# bbc_micro.net
KiCad netlist of a schematic drawn in EAGLE
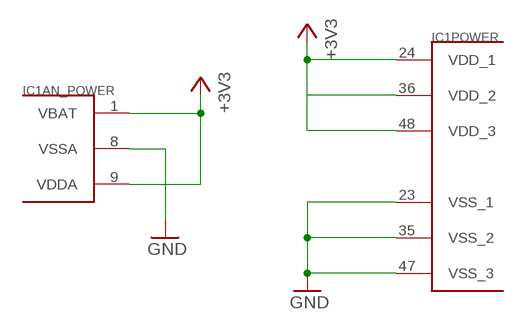
[diagram p0: schematic, sheet 1, part 1 of 2]
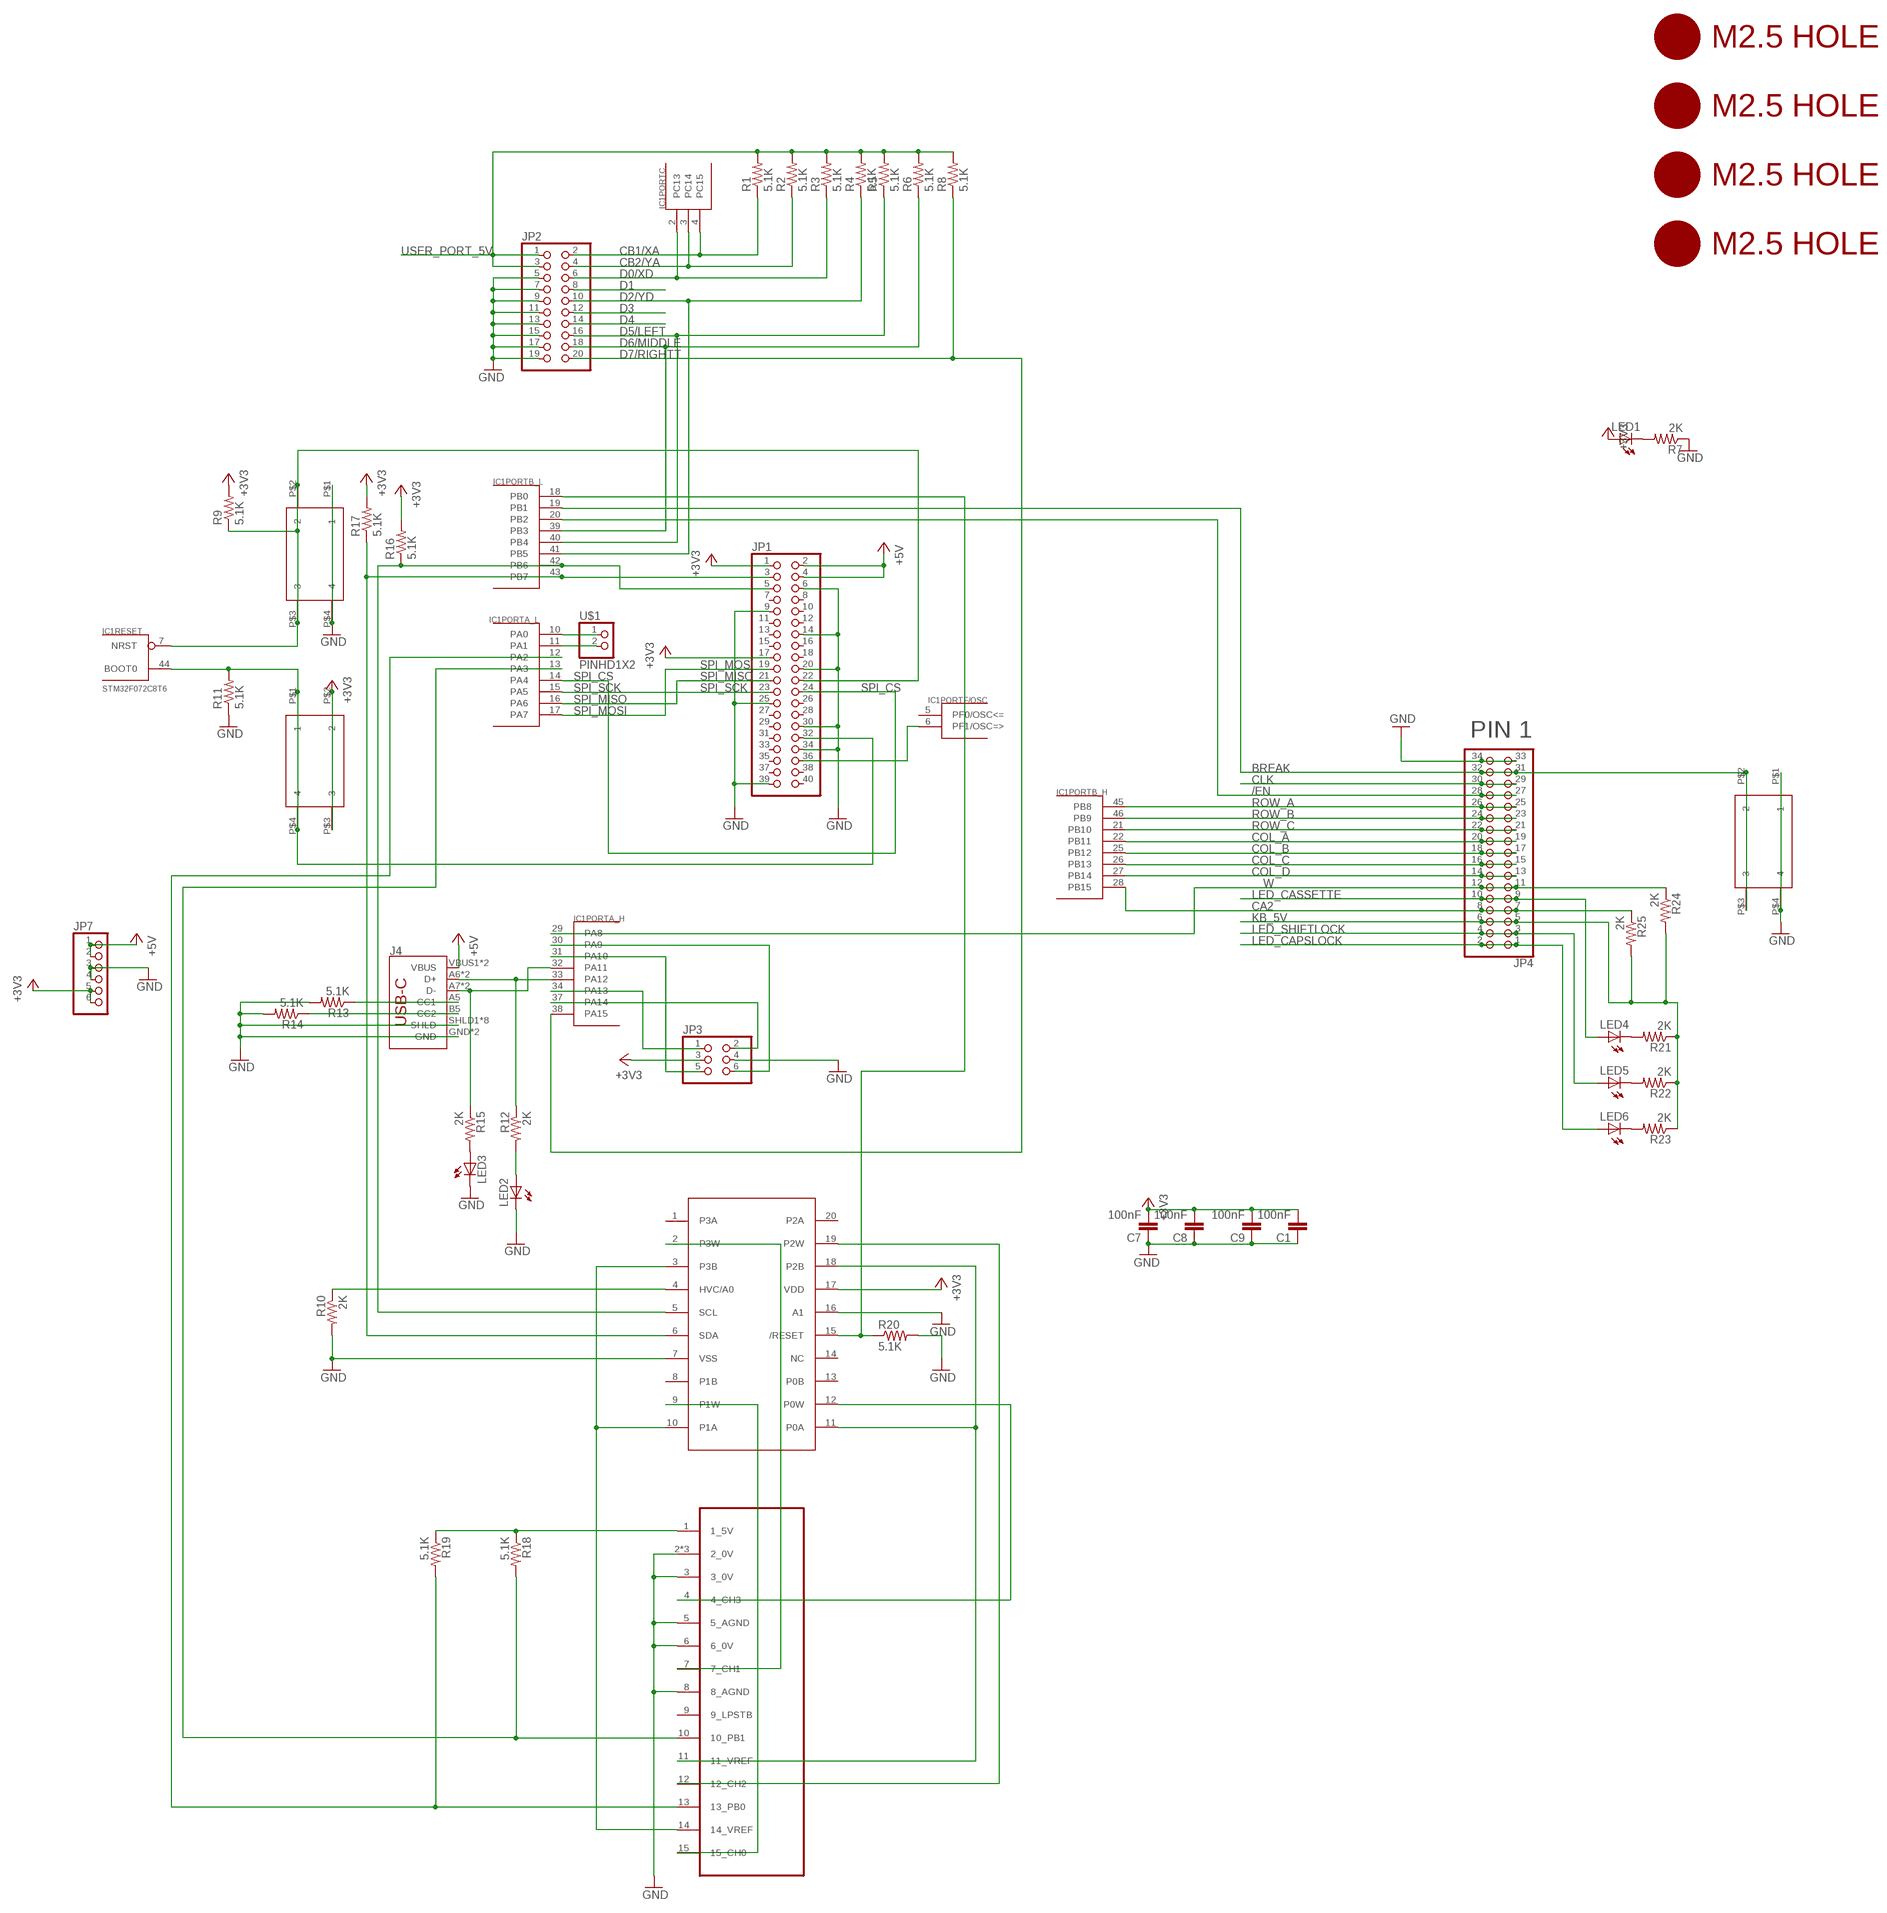
[diagram p1: schematic, sheet 1, part 2 of 2]

(export (version "E")
  (design (tool "Eeschema 10.0.6"))
  (components
    (comp (ref "C1")
      (value "100nF")
      (footprint "eagle-import:0805@1")
      (libsource (lib "eagle-import") (part "CAP0805"))
    )
    (comp (ref "C7")
      (value "100nF")
      (footprint "eagle-import:0805@1")
      (libsource (lib "eagle-import") (part "CAP0805"))
    )
    (comp (ref "C8")
      (value "100nF")
      (footprint "eagle-import:0805@1")
      (libsource (lib "eagle-import") (part "CAP0805"))
    )
    (comp (ref "C9")
      (value "100nF")
      (footprint "eagle-import:0805@1")
      (libsource (lib "eagle-import") (part "CAP0805"))
    )
    (comp (ref "IC1")
      (value "STM32F072C8T6")
      (footprint "eagle-import:TQFP48")
      (libsource (lib "eagle-import") (part "STM32F072C8T6"))
    )
    (comp (ref "J4")
      (value "USB_C16PIN")
      (footprint "eagle-import:USB-C-16P")
      (libsource (lib "eagle-import") (part "USB_C16PIN"))
    )
    (comp (ref "JP1")
      (value "PINHD-2X20-BIG")
      (footprint "eagle-import:2X20-BIG")
      (libsource (lib "eagle-import") (part "PINHD-2X20-BIG"))
    )
    (comp (ref "JP2")
      (value "PINHD-2X10/90")
      (footprint "eagle-import:2X10_90")
      (libsource (lib "eagle-import") (part "PINHD-2X10/90"))
    )
    (comp (ref "JP3")
      (value "PINHD-2X3")
      (footprint "eagle-import:2X03")
      (libsource (lib "eagle-import") (part "PINHD-2X3"))
    )
    (comp (ref "JP4")
      (value "PINHD-2X17/90")
      (footprint "eagle-import:2X17_90")
      (libsource (lib "eagle-import") (part "PINHD-2X17/90"))
    )
    (comp (ref "JP7")
      (value "PINHD-1X6CB")
      (footprint "eagle-import:1X06-CLEANBIG")
      (libsource (lib "eagle-import") (part "PINHD-1X6CB"))
    )
    (comp (ref "LED1")
      (value "LEDCHIP-LED0805")
      (footprint "eagle-import:CHIP-LED0805")
      (libsource (lib "eagle-import") (part "LEDCHIP-LED0805"))
    )
    (comp (ref "LED2")
      (value "LEDCHIP-LED0805")
      (footprint "eagle-import:CHIP-LED0805")
      (libsource (lib "eagle-import") (part "LEDCHIP-LED0805"))
    )
    (comp (ref "LED3")
      (value "LEDCHIP-LED0805")
      (footprint "eagle-import:CHIP-LED0805")
      (libsource (lib "eagle-import") (part "LEDCHIP-LED0805"))
    )
    (comp (ref "LED4")
      (value "LEDCHIP-LED0805")
      (footprint "eagle-import:CHIP-LED0805")
      (libsource (lib "eagle-import") (part "LEDCHIP-LED0805"))
    )
    (comp (ref "LED5")
      (value "LEDCHIP-LED0805")
      (footprint "eagle-import:CHIP-LED0805")
      (libsource (lib "eagle-import") (part "LEDCHIP-LED0805"))
    )
    (comp (ref "LED6")
      (value "LEDCHIP-LED0805")
      (footprint "eagle-import:CHIP-LED0805")
      (libsource (lib "eagle-import") (part "LEDCHIP-LED0805"))
    )
    (comp (ref "R1")
      (value "5.1K")
      (footprint "eagle-import:0805")
      (libsource (lib "eagle-import") (part "RESISTOR0805-RES"))
    )
    (comp (ref "R2")
      (value "5.1K")
      (footprint "eagle-import:0805")
      (libsource (lib "eagle-import") (part "RESISTOR0805-RES"))
    )
    (comp (ref "R3")
      (value "5.1K")
      (footprint "eagle-import:0805")
      (libsource (lib "eagle-import") (part "RESISTOR0805-RES"))
    )
    (comp (ref "R4")
      (value "5.1K")
      (footprint "eagle-import:0805")
      (libsource (lib "eagle-import") (part "RESISTOR0805-RES"))
    )
    (comp (ref "R5")
      (value "5.1K")
      (footprint "eagle-import:0805")
      (libsource (lib "eagle-import") (part "RESISTOR0805-RES"))
    )
    (comp (ref "R6")
      (value "5.1K")
      (footprint "eagle-import:0805")
      (libsource (lib "eagle-import") (part "RESISTOR0805-RES"))
    )
    (comp (ref "R7")
      (value "2K")
      (footprint "eagle-import:0805")
      (libsource (lib "eagle-import") (part "RESISTOR0805-RES"))
    )
    (comp (ref "R8")
      (value "5.1K")
      (footprint "eagle-import:0805")
      (libsource (lib "eagle-import") (part "RESISTOR0805-RES"))
    )
    (comp (ref "R9")
      (value "5.1K")
      (footprint "eagle-import:0805")
      (libsource (lib "eagle-import") (part "RESISTOR0805-RES"))
    )
    (comp (ref "R10")
      (value "2K")
      (footprint "eagle-import:0805")
      (libsource (lib "eagle-import") (part "RESISTOR0805-RES"))
    )
    (comp (ref "R11")
      (value "5.1K")
      (footprint "eagle-import:0805")
      (libsource (lib "eagle-import") (part "RESISTOR0805-RES"))
    )
    (comp (ref "R12")
      (value "2K")
      (footprint "eagle-import:0805")
      (libsource (lib "eagle-import") (part "RESISTOR0805-RES"))
    )
    (comp (ref "R13")
      (value "5.1K")
      (footprint "eagle-import:0805")
      (libsource (lib "eagle-import") (part "RESISTOR0805-RES"))
    )
    (comp (ref "R14")
      (value "5.1K")
      (footprint "eagle-import:0805")
      (libsource (lib "eagle-import") (part "RESISTOR0805-RES"))
    )
    (comp (ref "R15")
      (value "2K")
      (footprint "eagle-import:0805")
      (libsource (lib "eagle-import") (part "RESISTOR0805-RES"))
    )
    (comp (ref "R16")
      (value "5.1K")
      (footprint "eagle-import:0805")
      (libsource (lib "eagle-import") (part "RESISTOR0805-RES"))
    )
    (comp (ref "R17")
      (value "5.1K")
      (footprint "eagle-import:0805")
      (libsource (lib "eagle-import") (part "RESISTOR0805-RES"))
    )
    (comp (ref "R18")
      (value "5.1K")
      (footprint "eagle-import:0805")
      (libsource (lib "eagle-import") (part "RESISTOR0805-RES"))
    )
    (comp (ref "R19")
      (value "5.1K")
      (footprint "eagle-import:0805")
      (libsource (lib "eagle-import") (part "RESISTOR0805-RES"))
    )
    (comp (ref "R20")
      (value "5.1K")
      (footprint "eagle-import:0805")
      (libsource (lib "eagle-import") (part "RESISTOR0805-RES"))
    )
    (comp (ref "R21")
      (value "2K")
      (footprint "eagle-import:0805")
      (libsource (lib "eagle-import") (part "RESISTOR0805-RES"))
    )
    (comp (ref "R22")
      (value "2K")
      (footprint "eagle-import:0805")
      (libsource (lib "eagle-import") (part "RESISTOR0805-RES"))
    )
    (comp (ref "R23")
      (value "2K")
      (footprint "eagle-import:0805")
      (libsource (lib "eagle-import") (part "RESISTOR0805-RES"))
    )
    (comp (ref "R24")
      (value "2K")
      (footprint "eagle-import:0805")
      (libsource (lib "eagle-import") (part "RESISTOR0805-RES"))
    )
    (comp (ref "R25")
      (value "2K")
      (footprint "eagle-import:0805")
      (libsource (lib "eagle-import") (part "RESISTOR0805-RES"))
    )
    (comp (ref "SW1")
      (value "324_SW")
      (footprint "eagle-import:342_SWICH_FOOT")
      (libsource (lib "eagle-import") (part "324_SW"))
    )
    (comp (ref "SW2")
      (value "324_SW")
      (footprint "eagle-import:342_SWICH_FOOT")
      (libsource (lib "eagle-import") (part "324_SW"))
    )
    (comp (ref "SW3")
      (value "324_SW")
      (footprint "eagle-import:342_SWICH_FOOT")
      (libsource (lib "eagle-import") (part "324_SW"))
    )
    (comp (ref "U$1")
      (value "PINHD1X2")
      (footprint "eagle-import:1X02")
      (libsource (lib "eagle-import") (part "PINHD1X2"))
    )
    (comp (ref "U$2")
      (value "M2.5HOLE")
      (footprint "eagle-import:M2.5HOLE")
      (libsource (lib "eagle-import") (part "M2.5HOLE"))
    )
    (comp (ref "U$3")
      (value "M2.5HOLE")
      (footprint "eagle-import:M2.5HOLE")
      (libsource (lib "eagle-import") (part "M2.5HOLE"))
    )
    (comp (ref "U$5")
      (value "MCP4451")
      (footprint "eagle-import:TSSOP20")
      (libsource (lib "eagle-import") (part "MCP4451"))
    )
    (comp (ref "U$6")
      (value "M2.5HOLE")
      (footprint "eagle-import:M2.5HOLE")
      (libsource (lib "eagle-import") (part "M2.5HOLE"))
    )
    (comp (ref "U$7")
      (value "M2.5HOLE")
      (footprint "eagle-import:M2.5HOLE")
      (libsource (lib "eagle-import") (part "M2.5HOLE"))
    )
    (comp (ref "U$9")
      (value "BBC_15P")
      (footprint "eagle-import:DA15")
      (libsource (lib "eagle-import") (part "BBC_15P"))
    )
  )
  (nets
    (net (code "1") (name "+3V3") (class "Default")
      (node (ref "C1") (pin "2") (pinfunction "2_2") (pintype "passive"))
      (node (ref "C7") (pin "2") (pinfunction "2_2") (pintype "passive"))
      (node (ref "C8") (pin "2") (pinfunction "2_2") (pintype "passive"))
      (node (ref "C9") (pin "2") (pinfunction "2_2") (pintype "passive"))
      (node (ref "IC1") (pin "1") (pinfunction "VBAT_1") (pintype "power_in"))
      (node (ref "IC1") (pin "24") (pinfunction "VDD_1_24") (pintype "power_in"))
      (node (ref "IC1") (pin "36") (pinfunction "VDD_2_36") (pintype "power_in"))
      (node (ref "IC1") (pin "48") (pinfunction "VDD_3_48") (pintype "power_in"))
      (node (ref "IC1") (pin "9") (pinfunction "VDDA_9") (pintype "power_in"))
      (node (ref "JP1") (pin "1") (pinfunction "1_1") (pintype "passive"))
      (node (ref "JP1") (pin "17") (pinfunction "17_17") (pintype "passive"))
      (node (ref "JP3") (pin "3") (pinfunction "3_3") (pintype "passive"))
      (node (ref "JP7") (pin "5") (pinfunction "5_5") (pintype "passive"))
      (node (ref "JP7") (pin "6") (pinfunction "6_6") (pintype "passive"))
      (node (ref "LED1") (pin "A") (pinfunction "A_A") (pintype "passive"))
      (node (ref "R16") (pin "2") (pinfunction "2_2") (pintype "passive"))
      (node (ref "R17") (pin "2") (pinfunction "2_2") (pintype "passive"))
      (node (ref "R9") (pin "2") (pinfunction "2_2") (pintype "passive"))
      (node (ref "SW2") (pin "P$2") (pinfunction "2_P$2") (pintype "bidirectional"))
      (node (ref "SW2") (pin "P$3") (pinfunction "3_P$3") (pintype "bidirectional"))
      (node (ref "U$5") (pin "17") (pinfunction "VDD_17") (pintype "bidirectional"))
    )
    (net (code "2") (name "+5V") (class "Default")
      (node (ref "J4") (pin "VBUS1") (pinfunction "VBUS_VBUS1") (pintype "bidirectional"))
      (node (ref "J4") (pin "VBUS2") (pinfunction "VBUS_VBUS2") (pintype "bidirectional"))
      (node (ref "JP1") (pin "2") (pinfunction "2_2") (pintype "passive"))
      (node (ref "JP1") (pin "4") (pinfunction "4_4") (pintype "passive"))
      (node (ref "JP7") (pin "1") (pinfunction "1_1") (pintype "passive"))
      (node (ref "JP7") (pin "2") (pinfunction "2_2") (pintype "passive"))
    )
    (net (code "3") (name "/BREAK") (class "Default")
      (node (ref "IC1") (pin "19") (pinfunction "PB1_19") (pintype "bidirectional"))
      (node (ref "JP4") (pin "31") (pinfunction "31_31") (pintype "passive"))
      (node (ref "JP4") (pin "32") (pinfunction "32_32") (pintype "passive"))
      (node (ref "SW3") (pin "P$2") (pinfunction "2_P$2") (pintype "bidirectional"))
      (node (ref "SW3") (pin "P$3") (pinfunction "3_P$3") (pintype "bidirectional"))
    )
    (net (code "4") (name "/CA2") (class "Default")
      (node (ref "IC1") (pin "28") (pinfunction "PB15_28") (pintype "bidirectional"))
      (node (ref "JP4") (pin "7") (pinfunction "7_7") (pintype "passive"))
      (node (ref "JP4") (pin "8") (pinfunction "8_8") (pintype "passive"))
      (node (ref "R25") (pin "1") (pinfunction "1_1") (pintype "passive"))
    )
    (net (code "5") (name "/CB1{slash}XA") (class "Default")
      (node (ref "IC1") (pin "4") (pinfunction "PC15_4") (pintype "bidirectional"))
      (node (ref "JP2") (pin "2") (pinfunction "2_2") (pintype "passive"))
      (node (ref "R1") (pin "1") (pinfunction "1_1") (pintype "passive"))
    )
    (net (code "6") (name "/CB2{slash}YA") (class "Default")
      (node (ref "IC1") (pin "3") (pinfunction "PC14_3") (pintype "bidirectional"))
      (node (ref "JP2") (pin "4") (pinfunction "4_4") (pintype "passive"))
      (node (ref "R2") (pin "1") (pinfunction "1_1") (pintype "passive"))
    )
    (net (code "7") (name "/CLK") (class "Default")
      (node (ref "JP4") (pin "29") (pinfunction "29_29") (pintype "passive"))
      (node (ref "JP4") (pin "30") (pinfunction "30_30") (pintype "passive"))
    )
    (net (code "8") (name "/COL_A") (class "Default")
      (node (ref "IC1") (pin "22") (pinfunction "PB11_22") (pintype "bidirectional"))
      (node (ref "JP4") (pin "19") (pinfunction "19_19") (pintype "passive"))
      (node (ref "JP4") (pin "20") (pinfunction "20_20") (pintype "passive"))
    )
    (net (code "9") (name "/COL_B") (class "Default")
      (node (ref "IC1") (pin "25") (pinfunction "PB12_25") (pintype "bidirectional"))
      (node (ref "JP4") (pin "17") (pinfunction "17_17") (pintype "passive"))
      (node (ref "JP4") (pin "18") (pinfunction "18_18") (pintype "passive"))
    )
    (net (code "10") (name "/COL_C") (class "Default")
      (node (ref "IC1") (pin "26") (pinfunction "PB13_26") (pintype "bidirectional"))
      (node (ref "JP4") (pin "15") (pinfunction "15_15") (pintype "passive"))
      (node (ref "JP4") (pin "16") (pinfunction "16_16") (pintype "passive"))
    )
    (net (code "11") (name "/COL_D") (class "Default")
      (node (ref "IC1") (pin "27") (pinfunction "PB14_27") (pintype "bidirectional"))
      (node (ref "JP4") (pin "13") (pinfunction "13_13") (pintype "passive"))
      (node (ref "JP4") (pin "14") (pinfunction "14_14") (pintype "passive"))
    )
    (net (code "12") (name "/D0{slash}XD") (class "Default")
      (node (ref "IC1") (pin "2") (pinfunction "PC13_2") (pintype "bidirectional"))
      (node (ref "JP2") (pin "6") (pinfunction "6_6") (pintype "passive"))
      (node (ref "R3") (pin "1") (pinfunction "1_1") (pintype "passive"))
    )
    (net (code "13") (name "/D1") (class "Default")
      (node (ref "JP2") (pin "8") (pinfunction "8_8") (pintype "passive"))
    )
    (net (code "14") (name "/D2{slash}YD") (class "Default")
      (node (ref "IC1") (pin "41") (pinfunction "PB5_41") (pintype "bidirectional"))
      (node (ref "JP2") (pin "10") (pinfunction "10_10") (pintype "passive"))
      (node (ref "R4") (pin "1") (pinfunction "1_1") (pintype "passive"))
    )
    (net (code "15") (name "/D3") (class "Default")
      (node (ref "JP2") (pin "12") (pinfunction "12_12") (pintype "passive"))
    )
    (net (code "16") (name "/D4") (class "Default")
      (node (ref "JP2") (pin "14") (pinfunction "14_14") (pintype "passive"))
    )
    (net (code "17") (name "/D5{slash}LEFT") (class "Default")
      (node (ref "IC1") (pin "40") (pinfunction "PB4_40") (pintype "bidirectional"))
      (node (ref "JP2") (pin "16") (pinfunction "16_16") (pintype "passive"))
      (node (ref "R5") (pin "1") (pinfunction "1_1") (pintype "passive"))
    )
    (net (code "18") (name "/D6{slash}MIDDLE") (class "Default")
      (node (ref "IC1") (pin "39") (pinfunction "PB3_39") (pintype "bidirectional"))
      (node (ref "JP2") (pin "18") (pinfunction "18_18") (pintype "passive"))
      (node (ref "R6") (pin "1") (pinfunction "1_1") (pintype "passive"))
    )
    (net (code "19") (name "/D7{slash}RIGHTT") (class "Default")
      (node (ref "IC1") (pin "38") (pinfunction "PA15_38") (pintype "bidirectional"))
      (node (ref "JP2") (pin "20") (pinfunction "20_20") (pintype "passive"))
      (node (ref "R8") (pin "1") (pinfunction "1_1") (pintype "passive"))
    )
    (net (code "20") (name "/KB_5V") (class "Default")
      (node (ref "JP4") (pin "5") (pinfunction "5_5") (pintype "passive"))
      (node (ref "JP4") (pin "6") (pinfunction "6_6") (pintype "passive"))
      (node (ref "R21") (pin "1") (pinfunction "1_1") (pintype "passive"))
      (node (ref "R22") (pin "1") (pinfunction "1_1") (pintype "passive"))
      (node (ref "R23") (pin "1") (pinfunction "1_1") (pintype "passive"))
      (node (ref "R24") (pin "2") (pinfunction "2_2") (pintype "passive"))
      (node (ref "R25") (pin "2") (pinfunction "2_2") (pintype "passive"))
    )
    (net (code "21") (name "/LED_CAPSLOCK") (class "Default")
      (node (ref "JP4") (pin "1") (pinfunction "1_1") (pintype "passive"))
      (node (ref "JP4") (pin "2") (pinfunction "2_2") (pintype "passive"))
      (node (ref "LED6") (pin "A") (pinfunction "A_A") (pintype "passive"))
    )
    (net (code "22") (name "/LED_CASSETTE") (class "Default")
      (node (ref "JP4") (pin "10") (pinfunction "10_10") (pintype "passive"))
      (node (ref "JP4") (pin "9") (pinfunction "9_9") (pintype "passive"))
      (node (ref "LED4") (pin "A") (pinfunction "A_A") (pintype "passive"))
    )
    (net (code "23") (name "/LED_SHIFTLOCK") (class "Default")
      (node (ref "JP4") (pin "3") (pinfunction "3_3") (pintype "passive"))
      (node (ref "JP4") (pin "4") (pinfunction "4_4") (pintype "passive"))
      (node (ref "LED5") (pin "A") (pinfunction "A_A") (pintype "passive"))
    )
    (net (code "24") (name "/ROW_A") (class "Default")
      (node (ref "IC1") (pin "45") (pinfunction "PB8_45") (pintype "bidirectional"))
      (node (ref "JP4") (pin "25") (pinfunction "25_25") (pintype "passive"))
      (node (ref "JP4") (pin "26") (pinfunction "26_26") (pintype "passive"))
    )
    (net (code "25") (name "/ROW_B") (class "Default")
      (node (ref "IC1") (pin "46") (pinfunction "PB9_46") (pintype "bidirectional"))
      (node (ref "JP4") (pin "23") (pinfunction "23_23") (pintype "passive"))
      (node (ref "JP4") (pin "24") (pinfunction "24_24") (pintype "passive"))
    )
    (net (code "26") (name "/ROW_C") (class "Default")
      (node (ref "IC1") (pin "21") (pinfunction "PB10_21") (pintype "bidirectional"))
      (node (ref "JP4") (pin "21") (pinfunction "21_21") (pintype "passive"))
      (node (ref "JP4") (pin "22") (pinfunction "22_22") (pintype "passive"))
    )
    (net (code "27") (name "/SPI_CS") (class "Default")
      (node (ref "IC1") (pin "14") (pinfunction "PA4_14") (pintype "bidirectional"))
      (node (ref "JP1") (pin "24") (pinfunction "24_24") (pintype "passive"))
    )
    (net (code "28") (name "/SPI_MISO") (class "Default")
      (node (ref "IC1") (pin "16") (pinfunction "PA6_16") (pintype "bidirectional"))
      (node (ref "JP1") (pin "21") (pinfunction "21_21") (pintype "passive"))
    )
    (net (code "29") (name "/SPI_MOSI") (class "Default")
      (node (ref "IC1") (pin "17") (pinfunction "PA7_17") (pintype "bidirectional"))
      (node (ref "JP1") (pin "19") (pinfunction "19_19") (pintype "passive"))
    )
    (net (code "30") (name "/SPI_SCK") (class "Default")
      (node (ref "IC1") (pin "15") (pinfunction "PA5_15") (pintype "bidirectional"))
      (node (ref "JP1") (pin "23") (pinfunction "23_23") (pintype "passive"))
    )
    (net (code "31") (name "/USER_PORT_5V") (class "Default")
      (node (ref "JP2") (pin "1") (pinfunction "1_1") (pintype "passive"))
      (node (ref "JP2") (pin "3") (pinfunction "3_3") (pintype "passive"))
      (node (ref "R1") (pin "2") (pinfunction "2_2") (pintype "passive"))
      (node (ref "R2") (pin "2") (pinfunction "2_2") (pintype "passive"))
      (node (ref "R3") (pin "2") (pinfunction "2_2") (pintype "passive"))
      (node (ref "R4") (pin "2") (pinfunction "2_2") (pintype "passive"))
      (node (ref "R5") (pin "2") (pinfunction "2_2") (pintype "passive"))
      (node (ref "R6") (pin "2") (pinfunction "2_2") (pintype "passive"))
      (node (ref "R8") (pin "2") (pinfunction "2_2") (pintype "passive"))
    )
    (net (code "32") (name "/W") (class "Default")
      (node (ref "IC1") (pin "29") (pinfunction "PA8_29") (pintype "bidirectional"))
      (node (ref "JP4") (pin "11") (pinfunction "11_11") (pintype "passive"))
      (node (ref "JP4") (pin "12") (pinfunction "12_12") (pintype "passive"))
      (node (ref "R24") (pin "1") (pinfunction "1_1") (pintype "passive"))
    )
    (net (code "33") (name "/{slash}EN") (class "Default")
      (node (ref "IC1") (pin "20") (pinfunction "PB2_20") (pintype "bidirectional"))
      (node (ref "JP4") (pin "27") (pinfunction "27_27") (pintype "passive"))
      (node (ref "JP4") (pin "28") (pinfunction "28_28") (pintype "passive"))
    )
    (net (code "34") (name "GND") (class "Default")
      (node (ref "C1") (pin "1") (pinfunction "1_1") (pintype "passive"))
      (node (ref "C7") (pin "1") (pinfunction "1_1") (pintype "passive"))
      (node (ref "C8") (pin "1") (pinfunction "1_1") (pintype "passive"))
      (node (ref "C9") (pin "1") (pinfunction "1_1") (pintype "passive"))
      (node (ref "IC1") (pin "23") (pinfunction "VSS_1_23") (pintype "power_in"))
      (node (ref "IC1") (pin "35") (pinfunction "VSS_2_35") (pintype "power_in"))
      (node (ref "IC1") (pin "47") (pinfunction "VSS_3_47") (pintype "power_in"))
      (node (ref "IC1") (pin "8") (pinfunction "VSSA_8") (pintype "power_in"))
      (node (ref "J4") (pin "GND") (pinfunction "GND_GND") (pintype "bidirectional"))
      (node (ref "J4") (pin "GND2") (pinfunction "GND_GND2") (pintype "bidirectional"))
      (node (ref "J4") (pin "SHLD1") (pinfunction "SHLD_SHLD1") (pintype "bidirectional"))
      (node (ref "J4") (pin "SHLD2") (pinfunction "SHLD_SHLD2") (pintype "bidirectional"))
      (node (ref "J4") (pin "SHLD3") (pinfunction "SHLD_SHLD3") (pintype "bidirectional"))
      (node (ref "J4") (pin "SHLD4") (pinfunction "SHLD_SHLD4") (pintype "bidirectional"))
      (node (ref "J4") (pin "SHLD5") (pinfunction "SHLD_SHLD5") (pintype "bidirectional"))
      (node (ref "J4") (pin "SHLD6") (pinfunction "SHLD_SHLD6") (pintype "bidirectional"))
      (node (ref "J4") (pin "SHLD7") (pinfunction "SHLD_SHLD7") (pintype "bidirectional"))
      (node (ref "J4") (pin "SHLD8") (pinfunction "SHLD_SHLD8") (pintype "bidirectional"))
      (node (ref "JP1") (pin "14") (pinfunction "14_14") (pintype "passive"))
      (node (ref "JP1") (pin "20") (pinfunction "20_20") (pintype "passive"))
      (node (ref "JP1") (pin "25") (pinfunction "25_25") (pintype "passive"))
      (node (ref "JP1") (pin "30") (pinfunction "30_30") (pintype "passive"))
      (node (ref "JP1") (pin "34") (pinfunction "34_34") (pintype "passive"))
      (node (ref "JP1") (pin "39") (pinfunction "39_39") (pintype "passive"))
      (node (ref "JP1") (pin "6") (pinfunction "6_6") (pintype "passive"))
      (node (ref "JP1") (pin "9") (pinfunction "9_9") (pintype "passive"))
      (node (ref "JP2") (pin "11") (pinfunction "11_11") (pintype "passive"))
      (node (ref "JP2") (pin "13") (pinfunction "13_13") (pintype "passive"))
      (node (ref "JP2") (pin "15") (pinfunction "15_15") (pintype "passive"))
      (node (ref "JP2") (pin "17") (pinfunction "17_17") (pintype "passive"))
      (node (ref "JP2") (pin "19") (pinfunction "19_19") (pintype "passive"))
      (node (ref "JP2") (pin "5") (pinfunction "5_5") (pintype "passive"))
      (node (ref "JP2") (pin "7") (pinfunction "7_7") (pintype "passive"))
      (node (ref "JP2") (pin "9") (pinfunction "9_9") (pintype "passive"))
      (node (ref "JP3") (pin "4") (pinfunction "4_4") (pintype "passive"))
      (node (ref "JP4") (pin "33") (pinfunction "33_33") (pintype "passive"))
      (node (ref "JP4") (pin "34") (pinfunction "34_34") (pintype "passive"))
      (node (ref "JP7") (pin "3") (pinfunction "3_3") (pintype "passive"))
      (node (ref "JP7") (pin "4") (pinfunction "4_4") (pintype "passive"))
      (node (ref "LED2") (pin "C") (pinfunction "C_C") (pintype "passive"))
      (node (ref "LED3") (pin "C") (pinfunction "C_C") (pintype "passive"))
      (node (ref "R10") (pin "2") (pinfunction "2_2") (pintype "passive"))
      (node (ref "R11") (pin "1") (pinfunction "1_1") (pintype "passive"))
      (node (ref "R13") (pin "2") (pinfunction "2_2") (pintype "passive"))
      (node (ref "R14") (pin "2") (pinfunction "2_2") (pintype "passive"))
      (node (ref "R20") (pin "2") (pinfunction "2_2") (pintype "passive"))
      (node (ref "R7") (pin "1") (pinfunction "1_1") (pintype "passive"))
      (node (ref "SW1") (pin "P$1") (pinfunction "1_P$1") (pintype "bidirectional"))
      (node (ref "SW1") (pin "P$4") (pinfunction "4_P$4") (pintype "bidirectional"))
      (node (ref "SW3") (pin "P$1") (pinfunction "1_P$1") (pintype "bidirectional"))
      (node (ref "SW3") (pin "P$4") (pinfunction "4_P$4") (pintype "bidirectional"))
      (node (ref "U$5") (pin "16") (pinfunction "A1_16") (pintype "bidirectional"))
      (node (ref "U$5") (pin "7") (pinfunction "VSS_7") (pintype "bidirectional"))
      (node (ref "U$9") (pin "2") (pinfunction "2_0V_2") (pintype "bidirectional"))
      (node (ref "U$9") (pin "3") (pinfunction "3_0V_3") (pintype "bidirectional"))
      (node (ref "U$9") (pin "5") (pinfunction "5_AGND_5") (pintype "bidirectional"))
      (node (ref "U$9") (pin "6") (pinfunction "6_0V_6") (pintype "bidirectional"))
      (node (ref "U$9") (pin "8") (pinfunction "8_AGND_8") (pintype "bidirectional"))
      (node (ref "U$9") (pin "G1") (pinfunction "2_0V_G1") (pintype "bidirectional"))
      (node (ref "U$9") (pin "G2") (pinfunction "2_0V_G2") (pintype "bidirectional"))
    )
    (net (code "35") (name "Net-(IC1B-PA9)") (class "Default")
      (node (ref "IC1") (pin "30") (pinfunction "PA9_30") (pintype "bidirectional"))
      (node (ref "JP3") (pin "6") (pinfunction "6_6") (pintype "passive"))
    )
    (net (code "36") (name "Net-(IC1B-PA10)") (class "Default")
      (node (ref "IC1") (pin "31") (pinfunction "PA10_31") (pintype "bidirectional"))
      (node (ref "JP3") (pin "5") (pinfunction "5_5") (pintype "passive"))
    )
    (net (code "37") (name "Net-(IC1B-PA11)") (class "Default")
      (node (ref "IC1") (pin "32") (pinfunction "PA11_32") (pintype "bidirectional"))
      (node (ref "J4") (pin "A7") (pinfunction "D-_A7") (pintype "bidirectional"))
      (node (ref "J4") (pin "B7") (pinfunction "D-_B7") (pintype "bidirectional"))
      (node (ref "R15") (pin "1") (pinfunction "1_1") (pintype "passive"))
    )
    (net (code "38") (name "Net-(IC1B-PA12)") (class "Default")
      (node (ref "IC1") (pin "33") (pinfunction "PA12_33") (pintype "bidirectional"))
      (node (ref "J4") (pin "A6") (pinfunction "D+_A6") (pintype "bidirectional"))
      (node (ref "J4") (pin "B6") (pinfunction "D+_B6") (pintype "bidirectional"))
      (node (ref "R12") (pin "1") (pinfunction "1_1") (pintype "passive"))
    )
    (net (code "39") (name "Net-(IC1B-PA13)") (class "Default")
      (node (ref "IC1") (pin "34") (pinfunction "PA13_34") (pintype "bidirectional"))
      (node (ref "JP3") (pin "1") (pinfunction "1_1") (pintype "passive"))
    )
    (net (code "40") (name "Net-(IC1B-PA14)") (class "Default")
      (node (ref "IC1") (pin "37") (pinfunction "PA14_37") (pintype "bidirectional"))
      (node (ref "JP3") (pin "2") (pinfunction "2_2") (pintype "passive"))
    )
    (net (code "41") (name "Net-(IC1C-PA0)") (class "Default")
      (node (ref "IC1") (pin "10") (pinfunction "PA0_10") (pintype "bidirectional"))
      (node (ref "U$1") (pin "1") (pinfunction "1_1") (pintype "passive"))
    )
    (net (code "42") (name "Net-(IC1C-PA1)") (class "Default")
      (node (ref "IC1") (pin "11") (pinfunction "PA1_11") (pintype "bidirectional"))
      (node (ref "U$1") (pin "2") (pinfunction "2_2") (pintype "passive"))
    )
    (net (code "43") (name "Net-(IC1C-PA2)") (class "Default")
      (node (ref "IC1") (pin "12") (pinfunction "PA2_12") (pintype "bidirectional"))
      (node (ref "R19") (pin "2") (pinfunction "2_2") (pintype "passive"))
      (node (ref "U$9") (pin "13") (pinfunction "13_PB0_13") (pintype "bidirectional"))
    )
    (net (code "44") (name "Net-(IC1C-PA3)") (class "Default")
      (node (ref "IC1") (pin "13") (pinfunction "PA3_13") (pintype "bidirectional"))
      (node (ref "R18") (pin "2") (pinfunction "2_2") (pintype "passive"))
      (node (ref "U$9") (pin "10") (pinfunction "10_PB1_10") (pintype "bidirectional"))
    )
    (net (code "45") (name "Net-(IC1E-PB0)") (class "Default")
      (node (ref "IC1") (pin "18") (pinfunction "PB0_18") (pintype "bidirectional"))
      (node (ref "R20") (pin "1") (pinfunction "1_1") (pintype "passive"))
      (node (ref "U$5") (pin "15") (pinfunction "/RESET_15") (pintype "bidirectional"))
    )
    (net (code "46") (name "Net-(IC1E-PB6)") (class "Default")
      (node (ref "IC1") (pin "42") (pinfunction "PB6_42") (pintype "bidirectional"))
      (node (ref "JP1") (pin "5") (pinfunction "5_5") (pintype "passive"))
      (node (ref "R16") (pin "1") (pinfunction "1_1") (pintype "passive"))
      (node (ref "U$5") (pin "5") (pinfunction "SCL_5") (pintype "bidirectional"))
    )
    (net (code "47") (name "Net-(IC1E-PB7)") (class "Default")
      (node (ref "IC1") (pin "43") (pinfunction "PB7_43") (pintype "bidirectional"))
      (node (ref "JP1") (pin "3") (pinfunction "3_3") (pintype "passive"))
      (node (ref "R17") (pin "1") (pinfunction "1_1") (pintype "passive"))
      (node (ref "U$5") (pin "6") (pinfunction "SDA_6") (pintype "bidirectional"))
    )
    (net (code "48") (name "Net-(IC1G-PF1{slash}OSC=>)") (class "Default")
      (node (ref "IC1") (pin "6") (pinfunction "PF1/OSC=>_6") (pintype "bidirectional"))
      (node (ref "JP1") (pin "36") (pinfunction "36_36") (pintype "passive"))
    )
    (net (code "49") (name "Net-(IC1I-BOOT0)") (class "Default")
      (node (ref "IC1") (pin "44") (pinfunction "BOOT0_44") (pintype "input"))
      (node (ref "JP1") (pin "32") (pinfunction "32_32") (pintype "passive"))
      (node (ref "R11") (pin "2") (pinfunction "2_2") (pintype "passive"))
      (node (ref "SW2") (pin "P$1") (pinfunction "1_P$1") (pintype "bidirectional"))
      (node (ref "SW2") (pin "P$4") (pinfunction "4_P$4") (pintype "bidirectional"))
    )
    (net (code "50") (name "Net-(IC1I-NRST)") (class "Default")
      (node (ref "IC1") (pin "7") (pinfunction "NRST_7") (pintype "input"))
      (node (ref "JP1") (pin "22") (pinfunction "22_22") (pintype "passive"))
      (node (ref "R9") (pin "1") (pinfunction "1_1") (pintype "passive"))
      (node (ref "SW1") (pin "P$2") (pinfunction "2_P$2") (pintype "bidirectional"))
      (node (ref "SW1") (pin "P$3") (pinfunction "3_P$3") (pintype "bidirectional"))
    )
    (net (code "51") (name "Net-(J4-CC1)") (class "Default")
      (node (ref "J4") (pin "A5") (pinfunction "CC1_A5") (pintype "bidirectional"))
      (node (ref "R13") (pin "1") (pinfunction "1_1") (pintype "passive"))
    )
    (net (code "52") (name "Net-(J4-CC2)") (class "Default")
      (node (ref "J4") (pin "B5") (pinfunction "CC2_B5") (pintype "bidirectional"))
      (node (ref "R14") (pin "1") (pinfunction "1_1") (pintype "passive"))
    )
    (net (code "53") (name "Net-(LED1-PadC)") (class "Default")
      (node (ref "LED1") (pin "C") (pinfunction "C_C") (pintype "passive"))
      (node (ref "R7") (pin "2") (pinfunction "2_2") (pintype "passive"))
    )
    (net (code "54") (name "Net-(LED2-PadA)") (class "Default")
      (node (ref "LED2") (pin "A") (pinfunction "A_A") (pintype "passive"))
      (node (ref "R12") (pin "2") (pinfunction "2_2") (pintype "passive"))
    )
    (net (code "55") (name "Net-(LED3-PadA)") (class "Default")
      (node (ref "LED3") (pin "A") (pinfunction "A_A") (pintype "passive"))
      (node (ref "R15") (pin "2") (pinfunction "2_2") (pintype "passive"))
    )
    (net (code "56") (name "Net-(LED4-PadC)") (class "Default")
      (node (ref "LED4") (pin "C") (pinfunction "C_C") (pintype "passive"))
      (node (ref "R21") (pin "2") (pinfunction "2_2") (pintype "passive"))
    )
    (net (code "57") (name "Net-(LED5-PadC)") (class "Default")
      (node (ref "LED5") (pin "C") (pinfunction "C_C") (pintype "passive"))
      (node (ref "R22") (pin "2") (pinfunction "2_2") (pintype "passive"))
    )
    (net (code "58") (name "Net-(LED6-PadC)") (class "Default")
      (node (ref "LED6") (pin "C") (pinfunction "C_C") (pintype "passive"))
      (node (ref "R23") (pin "2") (pinfunction "2_2") (pintype "passive"))
    )
    (net (code "59") (name "Net-(U$5-HVC{slash}A0)") (class "Default")
      (node (ref "R10") (pin "1") (pinfunction "1_1") (pintype "passive"))
      (node (ref "U$5") (pin "4") (pinfunction "HVC/A0_4") (pintype "bidirectional"))
    )
    (net (code "60") (name "Net-(U$5-P0A)") (class "Default")
      (node (ref "U$5") (pin "11") (pinfunction "P0A_11") (pintype "bidirectional"))
      (node (ref "U$5") (pin "18") (pinfunction "P2B_18") (pintype "bidirectional"))
      (node (ref "U$9") (pin "11") (pinfunction "11_VREF_11") (pintype "bidirectional"))
    )
    (net (code "61") (name "Net-(U$5-P0W)") (class "Default")
      (node (ref "U$5") (pin "12") (pinfunction "P0W_12") (pintype "bidirectional"))
      (node (ref "U$9") (pin "4") (pinfunction "4_CH3_4") (pintype "bidirectional"))
    )
    (net (code "62") (name "Net-(U$5-P1A)") (class "Default")
      (node (ref "U$5") (pin "10") (pinfunction "P1A_10") (pintype "bidirectional"))
      (node (ref "U$5") (pin "3") (pinfunction "P3B_3") (pintype "bidirectional"))
      (node (ref "U$9") (pin "14") (pinfunction "14_VREF_14") (pintype "bidirectional"))
    )
    (net (code "63") (name "Net-(U$5-P1W)") (class "Default")
      (node (ref "U$5") (pin "9") (pinfunction "P1W_9") (pintype "bidirectional"))
      (node (ref "U$9") (pin "15") (pinfunction "15_CH0_15") (pintype "bidirectional"))
    )
    (net (code "64") (name "Net-(U$5-P2W)") (class "Default")
      (node (ref "U$5") (pin "19") (pinfunction "P2W_19") (pintype "bidirectional"))
      (node (ref "U$9") (pin "12") (pinfunction "12_CH2_12") (pintype "bidirectional"))
    )
    (net (code "65") (name "Net-(U$5-P3W)") (class "Default")
      (node (ref "U$5") (pin "2") (pinfunction "P3W_2") (pintype "bidirectional"))
      (node (ref "U$9") (pin "7") (pinfunction "7_CH1_7") (pintype "bidirectional"))
    )
    (net (code "66") (name "Net-(U$9-1_5V)") (class "Default")
      (node (ref "R18") (pin "1") (pinfunction "1_1") (pintype "passive"))
      (node (ref "R19") (pin "1") (pinfunction "1_1") (pintype "passive"))
      (node (ref "U$9") (pin "1") (pinfunction "1_5V_1") (pintype "bidirectional"))
    )
    (net (code "67") (name "unconnected-(IC1G-PF0{slash}OSC<=-Pad5)") (class "Default")
      (node (ref "IC1") (pin "5") (pinfunction "PF0/OSC<=_5") (pintype "bidirectional"))
    )
    (net (code "68") (name "unconnected-(JP1-Pad7)") (class "Default")
      (node (ref "JP1") (pin "7") (pinfunction "7_7") (pintype "passive"))
    )
    (net (code "69") (name "unconnected-(JP1-Pad8)") (class "Default")
      (node (ref "JP1") (pin "8") (pinfunction "8_8") (pintype "passive"))
    )
    (net (code "70") (name "unconnected-(JP1-Pad10)") (class "Default")
      (node (ref "JP1") (pin "10") (pinfunction "10_10") (pintype "passive"))
    )
    (net (code "71") (name "unconnected-(JP1-Pad11)") (class "Default")
      (node (ref "JP1") (pin "11") (pinfunction "11_11") (pintype "passive"))
    )
    (net (code "72") (name "unconnected-(JP1-Pad12)") (class "Default")
      (node (ref "JP1") (pin "12") (pinfunction "12_12") (pintype "passive"))
    )
    (net (code "73") (name "unconnected-(JP1-Pad13)") (class "Default")
      (node (ref "JP1") (pin "13") (pinfunction "13_13") (pintype "passive"))
    )
    (net (code "74") (name "unconnected-(JP1-Pad15)") (class "Default")
      (node (ref "JP1") (pin "15") (pinfunction "15_15") (pintype "passive"))
    )
    (net (code "75") (name "unconnected-(JP1-Pad16)") (class "Default")
      (node (ref "JP1") (pin "16") (pinfunction "16_16") (pintype "passive"))
    )
    (net (code "76") (name "unconnected-(JP1-Pad18)") (class "Default")
      (node (ref "JP1") (pin "18") (pinfunction "18_18") (pintype "passive"))
    )
    (net (code "77") (name "unconnected-(JP1-Pad26)") (class "Default")
      (node (ref "JP1") (pin "26") (pinfunction "26_26") (pintype "passive"))
    )
    (net (code "78") (name "unconnected-(JP1-Pad27)") (class "Default")
      (node (ref "JP1") (pin "27") (pinfunction "27_27") (pintype "passive"))
    )
    (net (code "79") (name "unconnected-(JP1-Pad28)") (class "Default")
      (node (ref "JP1") (pin "28") (pinfunction "28_28") (pintype "passive"))
    )
    (net (code "80") (name "unconnected-(JP1-Pad29)") (class "Default")
      (node (ref "JP1") (pin "29") (pinfunction "29_29") (pintype "passive"))
    )
    (net (code "81") (name "unconnected-(JP1-Pad31)") (class "Default")
      (node (ref "JP1") (pin "31") (pinfunction "31_31") (pintype "passive"))
    )
    (net (code "82") (name "unconnected-(JP1-Pad33)") (class "Default")
      (node (ref "JP1") (pin "33") (pinfunction "33_33") (pintype "passive"))
    )
    (net (code "83") (name "unconnected-(JP1-Pad35)") (class "Default")
      (node (ref "JP1") (pin "35") (pinfunction "35_35") (pintype "passive"))
    )
    (net (code "84") (name "unconnected-(JP1-Pad37)") (class "Default")
      (node (ref "JP1") (pin "37") (pinfunction "37_37") (pintype "passive"))
    )
    (net (code "85") (name "unconnected-(JP1-Pad38)") (class "Default")
      (node (ref "JP1") (pin "38") (pinfunction "38_38") (pintype "passive"))
    )
    (net (code "86") (name "unconnected-(JP1-Pad40)") (class "Default")
      (node (ref "JP1") (pin "40") (pinfunction "40_40") (pintype "passive"))
    )
    (net (code "87") (name "unconnected-(U$5-NC-Pad14)") (class "Default")
      (node (ref "U$5") (pin "14") (pinfunction "NC_14") (pintype "bidirectional"))
    )
    (net (code "88") (name "unconnected-(U$5-P0B-Pad13)") (class "Default")
      (node (ref "U$5") (pin "13") (pinfunction "P0B_13") (pintype "bidirectional"))
    )
    (net (code "89") (name "unconnected-(U$5-P1B-Pad8)") (class "Default")
      (node (ref "U$5") (pin "8") (pinfunction "P1B_8") (pintype "bidirectional"))
    )
    (net (code "90") (name "unconnected-(U$5-P2A-Pad20)") (class "Default")
      (node (ref "U$5") (pin "20") (pinfunction "P2A_20") (pintype "bidirectional"))
    )
    (net (code "91") (name "unconnected-(U$5-P3A-Pad1)") (class "Default")
      (node (ref "U$5") (pin "1") (pinfunction "P3A_1") (pintype "bidirectional"))
    )
    (net (code "92") (name "unconnected-(U$9-9_LPSTB-Pad9)") (class "Default")
      (node (ref "U$9") (pin "9") (pinfunction "9_LPSTB_9") (pintype "bidirectional"))
    )
  )
)
